# LTEW_WPC_RCVR.net
KiCad netlist of a schematic drawn in Altium Designer
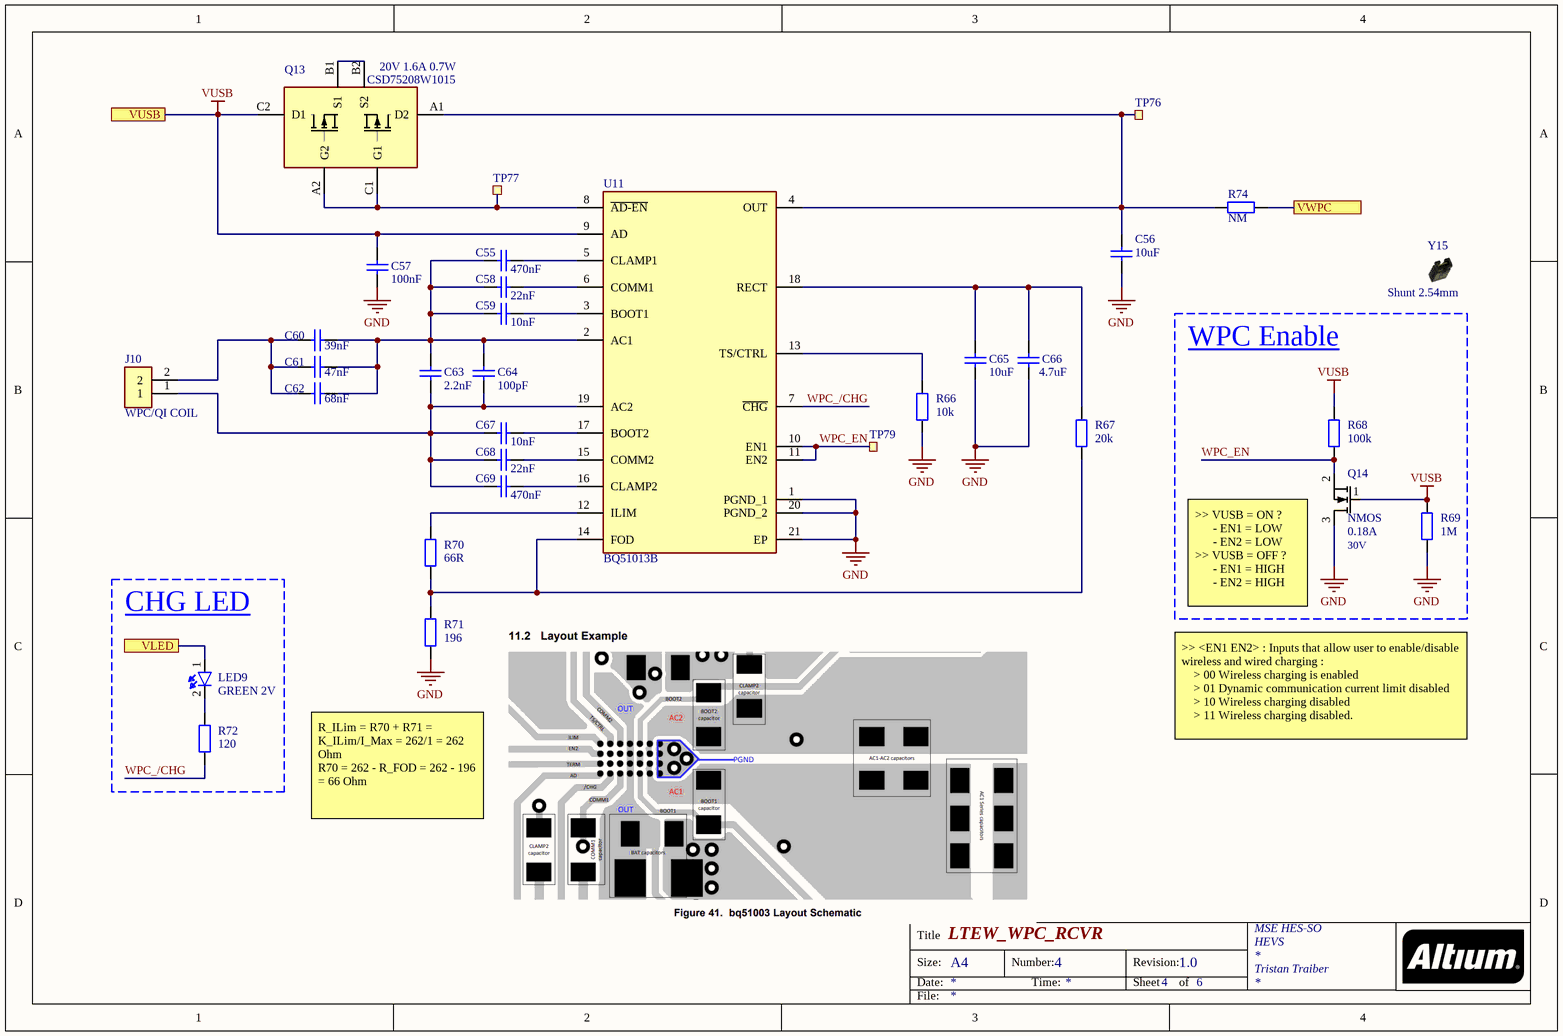
[diagram p0: LTEW_WPC_RCVR.SchDoc]

(export (version "E")
  (design (tool "Eeschema 10.0.6"))
  (components
    (comp (ref "C55")
      (value "470nF")
      (footprint "C0603")
      (description "0.47 µF ±10% 25V Ceramic Capacitor X7R 0603 (1608 Metric)")
      (fields (field (name "MANUFACTURER_PART_NUMBER") "GRM188R71E474KA12D"))
      (libsource (lib "LTEWlib") (part "C_470n"))
    )
    (comp (ref "C56")
      (value "10uF")
      (footprint "C0603")
      (description "10 µF ±10% 25V Ceramic Capacitor X5R 0805 (2012 Metric)")
      (fields (field (name "MANUFACTURER_PART_NUMBER") "GRM188R61E106KA73J"))
      (libsource (lib "LTEWlib") (part "C_10u"))
    )
    (comp (ref "C57")
      (value "100nF")
      (footprint "C0603")
      (description "0.1 µF ±10% 25V Condensateurs céramique X7R 0603 (1608 métrique)")
      (fields (field (name "MANUFACTURER_PART_NUMBER") "CL10B104KA8NNNC"))
      (libsource (lib "LTEWlib") (part "C_100n"))
    )
    (comp (ref "C58")
      (value "22nF")
      (footprint "C0603")
      (description "0.022 µF ±10% 25V Ceramic Capacitor X7R 0603 (1608 Metric)")
      (fields (field (name "MANUFACTURER_PART_NUMBER") "C0603C223K3RAC7867"))
      (libsource (lib "LTEWlib") (part "C_22n"))
    )
    (comp (ref "C59")
      (value "10nF")
      (footprint "C0603")
      (description "10000 pF ±5% 25V Condensateurs céramique C0G, NP0 0603 (1608 métrique)")
      (fields (field (name "MANUFACTURER_PART_NUMBER") "C1608C0G1E103J080AA"))
      (libsource (lib "LTEWlib") (part "C_10n"))
    )
    (comp (ref "C60")
      (value "39nF")
      (footprint "C0603")
      (description "0.039 µF ±10% 50V Ceramic Capacitor X7R 0603 (1608 Metric)")
      (fields (field (name "MANUFACTURER_PART_NUMBER") "0603B393K500CT"))
      (libsource (lib "LTEWlib") (part "C_39n"))
    )
    (comp (ref "C61")
      (value "47nF")
      (footprint "C0603")
      (description "0.047 µF ±10% 25V Ceramic Capacitor X7R 0603 (1608 Metric)")
      (fields (field (name "MANUFACTURER_PART_NUMBER") "06033C473KAT2A"))
      (libsource (lib "LTEWlib") (part "C_47n"))
    )
    (comp (ref "C62")
      (value "68nF")
      (footprint "C0603")
      (description "0.068 µF ±10% 25V Ceramic Capacitor X7R 0603 (1608 Metric)")
      (fields (field (name "MANUFACTURER_PART_NUMBER") "0603B683K250CT"))
      (libsource (lib "LTEWlib") (part "C_68n"))
    )
    (comp (ref "C63")
      (value "2.2nF")
      (footprint "C0603")
      (description "2200 pF ±5% 25V Ceramic Capacitor X7R 0603 (1608 Metric)")
      (fields (field (name "MANUFACTURER_PART_NUMBER") "06033C222JAT2A"))
      (libsource (lib "LTEWlib") (part "C_2.2n"))
    )
    (comp (ref "C64")
      (value "100pF")
      (footprint "C0603")
      (description "100 pF ±5% 25V Ceramic Capacitor C0G, NP0 0603 (1608 Metric)")
      (fields (field (name "MANUFACTURER_PART_NUMBER") "06033A101JAT2A"))
      (libsource (lib "LTEWlib") (part "C_100p"))
    )
    (comp (ref "C65")
      (value "10uF")
      (footprint "C0603")
      (description "10 µF ±10% 25V Ceramic Capacitor X5R 0805 (2012 Metric)")
      (fields (field (name "MANUFACTURER_PART_NUMBER") "GRM188R61E106KA73J"))
      (libsource (lib "LTEWlib") (part "C_10u"))
    )
    (comp (ref "C66")
      (value "4.7uF")
      (footprint "C0603")
      (description "4.7 µF ±10% 25V Condensateurs céramique X6S 0603 (1608 métrique)")
      (fields (field (name "MANUFACTURER_PART_NUMBER") "GRM188C81E475KE11D"))
      (libsource (lib "LTEWlib") (part "C_4.7u"))
    )
    (comp (ref "C67")
      (value "10nF")
      (footprint "C0603")
      (description "10000 pF ±5% 25V Condensateurs céramique C0G, NP0 0603 (1608 métrique)")
      (fields (field (name "MANUFACTURER_PART_NUMBER") "C1608C0G1E103J080AA"))
      (libsource (lib "LTEWlib") (part "C_10n"))
    )
    (comp (ref "C68")
      (value "22nF")
      (footprint "C0603")
      (description "0.022 µF ±10% 25V Ceramic Capacitor X7R 0603 (1608 Metric)")
      (fields (field (name "MANUFACTURER_PART_NUMBER") "C0603C223K3RAC7867"))
      (libsource (lib "LTEWlib") (part "C_22n"))
    )
    (comp (ref "C69")
      (value "470nF")
      (footprint "C0603")
      (description "0.47 µF ±10% 25V Ceramic Capacitor X7R 0603 (1608 Metric)")
      (fields (field (name "MANUFACTURER_PART_NUMBER") "GRM188R71E474KA12D"))
      (libsource (lib "LTEWlib") (part "C_470n"))
    )
    (comp (ref "J10")
      (value "WPC/QI COIL")
      (footprint "LTEWlib:23839422")
      (description "2 Position Wire to Board Terminal Block Horizontal with Board 0.138\" (3.50mm) Surface Mount")
      (fields (field (name "MANUFACTURER_PART_NUMBER") "2383942-2"))
      (libsource (lib "LTEWlib") (part "CONN_WPC_IND"))
    )
    (comp (ref "LED9")
      (value "GREEN 2V")
      (footprint "LTEWlib:LEDC1608X80N")
      (description "Green 570nm LED Indication - Discrete 2V 0603 (1608 Metric)")
      (fields (field (name "MANUFACTURER_PART_NUMBER") "150060VS75000"))
      (libsource (lib "LTEWlib") (part "LED_G"))
    )
    (comp (ref "Q13")
      (value "20V 1.6A 0.7W")
      (footprint "LTEWlib:BGA6C50P2X3_95X145X62")
      (description "Mosfet Array 2 P-Channel (Dual) Common Source 20V 1.6A 750mW Surface Mount 6-DSBGA (1x1.5)")
      (fields (field (name "MANUFACTURER_PART_NUMBER") "CSD75208W1015"))
      (libsource (lib "LTEWlib") (part "MOS_2PCH"))
    )
    (comp (ref "Q14")
      (value "NMOS")
      (footprint "LTEWlib:SOT65P210X110-3N")
      (description "N-Channel 30 V 180mA (Ta) 260mW (Ta), 1.1W (Tc) Surface Mount SOT-323")
      (fields
        (field (name "MANUFACTURER_PART_NUMBER") "NX3020NAKW")
        (field (name "VALUE2") "0.18A")
        (field (name "ALTIUM_VALUE") "30V")
      )
      (libsource (lib "LTEWlib") (part "MOS-N"))
    )
    (comp (ref "R66")
      (value "10k")
      (footprint "RES0603")
      (description "10 kOhms ±1% 0.1W, 1/10W Chip Resistor 0603 (1608 Metric) Moisture Resistant Thick Film")
      (fields (field (name "MANUFACTURER_PART_NUMBER") "RC0805FR-0710KL"))
      (libsource (lib "LTEWlib") (part "R_10k"))
    )
    (comp (ref "R67")
      (value "20k")
      (footprint "RES0603")
      (description "20 kOhms ±1% 0.1W, 1/10W Chip Resistor 0603 (1608 Metric) Moisture Resistant Thick Film")
      (fields (field (name "MANUFACTURER_PART_NUMBER") "RC0805FR-0710KL"))
      (libsource (lib "LTEWlib") (part "R_20k"))
    )
    (comp (ref "R68")
      (value "100k")
      (footprint "RES0603")
      (description "RES SMD 100K OHM 1% 1/8W 0603")
      (fields (field (name "MANUFACTURER_PART_NUMBER") "RC0805FR-07100KL"))
      (libsource (lib "LTEWlib") (part "R_100k"))
    )
    (comp (ref "R69")
      (value "1M")
      (footprint "RES0603")
      (description "1 MOhms ±1% 0.1W, 1/10W Chip Resistor 0603 (1608 Metric) Automotive AEC-Q200 Thick Film")
      (fields (field (name "MANUFACTURER_PART_NUMBER") "ERJ-3EKF1004V"))
      (libsource (lib "LTEWlib") (part "R_1M"))
    )
    (comp (ref "R70")
      (value "66R")
      (footprint "RES0603")
      (description "66.5 Ohms ±1% 0.1W, 1/10W Chip Resistor 0603 (1608 Metric) Moisture Resistant Thick Film")
      (fields (field (name "MANUFACTURER_PART_NUMBER") "RC0603FR-0766R5L"))
      (libsource (lib "LTEWlib") (part "R_66"))
    )
    (comp (ref "R71")
      (value "196")
      (footprint "RES0603")
      (description "196 Ohms ±1% 0.1W, 1/10W Chip Resistor 0603 (1608 Metric) Moisture Resistant Thick Film")
      (fields (field (name "MANUFACTURER_PART_NUMBER") "RC0603FR-07196RL"))
      (libsource (lib "LTEWlib") (part "R_196"))
    )
    (comp (ref "R72")
      (value "120")
      (footprint "RES0603")
      (description "1 MOhms ±1% 0.1W, 1/10W Chip Resistor 0603 (1608 Metric) Automotive AEC-Q200 Thick Film")
      (fields (field (name "MANUFACTURER_PART_NUMBER") "CRGCQ0603F120R"))
      (libsource (lib "LTEWlib") (part "R_120"))
    )
    (comp (ref "R74")
      (value "NM")
      (footprint "RES0603")
      (description "8.66 MOhms ±1% 0,1W, 1/10W Pavé résistif 0603 (1608 métrique) AutomobileAEC-Q200 Couche épaisse")
      (fields (field (name "MANUFACTURER_PART_NUMBER") "CRCW06038M66FKEA"))
      (libsource (lib "LTEWlib") (part "R_8.66M"))
    )
    (comp (ref "TP76")
      (value "Ø1.0mm,SMD")
      (footprint "TP_SMD_Ø0.8mm")
      (description "0.8 mm circular SMD testpad")
      (fields
        (field (name "PART NUMBER") "TP_SMD_Ø1.0MM")
        (field (name "MANUFACTURER") "Nordic Semiconductor")
      )
      (libsource (lib "LTEWlib") (part "TP_SMD"))
    )
    (comp (ref "TP77")
      (value "Ø1.0mm,SMD")
      (footprint "TP_SMD_Ø0.8mm")
      (description "0.8 mm circular SMD testpad")
      (fields
        (field (name "PART NUMBER") "TP_SMD_Ø1.0MM")
        (field (name "MANUFACTURER") "Nordic Semiconductor")
      )
      (libsource (lib "") (part "TP_SMD_1"))
    )
    (comp (ref "TP79")
      (value "Ø1.0mm,SMD")
      (footprint "TP_SMD_Ø0.8mm")
      (description "0.8 mm circular SMD testpad")
      (fields
        (field (name "PART NUMBER") "TP_SMD_Ø1.0MM")
        (field (name "MANUFACTURER") "Nordic Semiconductor")
      )
      (libsource (lib "LTEWlib") (part "TP_SMD"))
    )
    (comp (ref "U11")
      (value "BQ51013B")
      (footprint "LTEWlib:BQ51050BRHLR")
      (description "Wireless Power Receiver PMIC 20-VQFN (3.5x4.5)")
      (fields (field (name "MANUFACTURER_PART_NUMBER") "BQ51013BRHLR"))
      (libsource (lib "LTEWlib") (part "IC_WPC_VQFN"))
    )
    (comp (ref "Y15")
      (value "Shunt 2.54mm")
      (footprint "Shunt_2.54mm_Horizontal")
      (description "Shunt Jumper 2.54mm Black")
      (fields (field (name "MANUFACTURER PART NUMBER") "SPC02SYAN"))
      (libsource (lib "LTEWlib") (part "SHUNT JUMPER 2.54mm BLACK GOLD Horizontal"))
    )
  )
  (nets
    (net (code "1") (name "/VLED") (class "Default")
      (node (ref "LED9") (pin "1") (pinfunction "A_1") (pintype "passive"))
    )
    (net (code "2") (name "/VWPC") (class "Default")
      (node (ref "R74") (pin "1") (pinfunction "1_1") (pintype "passive"))
    )
    (net (code "3") (name "/WPC_EN") (class "Default")
      (node (ref "Q14") (pin "2") (pinfunction "S_2") (pintype "passive"))
      (node (ref "R68") (pin "1") (pinfunction "1_1") (pintype "passive"))
      (node (ref "TP79") (pin "1") (pinfunction "1_1") (pintype "passive"))
      (node (ref "U11") (pin "10") (pinfunction "EN1_10") (pintype "passive"))
      (node (ref "U11") (pin "11") (pinfunction "EN2_11") (pintype "passive"))
    )
    (net (code "4") (name "/WPC_{slash}CHG") (class "Default")
      (node (ref "R72") (pin "1") (pinfunction "1_1") (pintype "passive"))
      (node (ref "U11") (pin "7") (pinfunction "~{CHG}_7") (pintype "passive"))
    )
    (net (code "5") (name "GND") (class "Default")
      (node (ref "C56") (pin "1") (pinfunction "1_1") (pintype "passive"))
      (node (ref "C57") (pin "1") (pinfunction "1_1") (pintype "passive"))
      (node (ref "C65") (pin "1") (pinfunction "1_1") (pintype "passive"))
      (node (ref "C66") (pin "1") (pinfunction "1_1") (pintype "passive"))
      (node (ref "Q14") (pin "3") (pinfunction "D_3") (pintype "passive"))
      (node (ref "R66") (pin "1") (pinfunction "1_1") (pintype "passive"))
      (node (ref "R69") (pin "1") (pinfunction "1_1") (pintype "passive"))
      (node (ref "R71") (pin "1") (pinfunction "1_1") (pintype "passive"))
      (node (ref "U11") (pin "1") (pinfunction "PGND_1_1") (pintype "passive"))
      (node (ref "U11") (pin "20") (pinfunction "PGND_2_20") (pintype "passive"))
      (node (ref "U11") (pin "21") (pinfunction "EP_21") (pintype "passive"))
    )
    (net (code "6") (name "Net-(C60-Pad1)") (class "Default")
      (node (ref "C60") (pin "1") (pinfunction "1_1") (pintype "passive"))
      (node (ref "C61") (pin "1") (pinfunction "1_1") (pintype "passive"))
      (node (ref "C62") (pin "1") (pinfunction "1_1") (pintype "passive"))
      (node (ref "J10") (pin "2") (pinfunction "2_2") (pintype "passive"))
    )
    (net (code "7") (name "Net-(LED9-K)") (class "Default")
      (node (ref "LED9") (pin "2") (pinfunction "K_2") (pintype "passive"))
      (node (ref "R72") (pin "2") (pinfunction "2_2") (pintype "passive"))
    )
    (net (code "8") (name "Net-(Q13-D2)") (class "Default")
      (node (ref "C56") (pin "2") (pinfunction "2_2") (pintype "passive"))
      (node (ref "Q13") (pin "A1") (pinfunction "D2_A1") (pintype "passive"))
      (node (ref "R74") (pin "2") (pinfunction "2_2") (pintype "passive"))
      (node (ref "TP76") (pin "1") (pinfunction "1_1") (pintype "passive"))
      (node (ref "U11") (pin "4") (pinfunction "OUT_4") (pintype "passive"))
    )
    (net (code "9") (name "Net-(Q13-G1)") (class "Default")
      (node (ref "Q13") (pin "A2") (pinfunction "G2_A2") (pintype "passive"))
      (node (ref "Q13") (pin "C1") (pinfunction "G1_C1") (pintype "passive"))
      (node (ref "TP77") (pin "1") (pinfunction "1_1") (pintype "passive"))
      (node (ref "U11") (pin "8") (pinfunction "~{AD-EN}_8") (pintype "passive"))
    )
    (net (code "10") (name "Net-(Q13-S1)") (class "Default")
      (node (ref "Q13") (pin "B1") (pinfunction "S1_B1") (pintype "passive"))
      (node (ref "Q13") (pin "B2") (pinfunction "S2_B2") (pintype "passive"))
    )
    (net (code "11") (name "Net-(U11-AC1)") (class "Default")
      (node (ref "C55") (pin "1") (pinfunction "1_1") (pintype "passive"))
      (node (ref "C58") (pin "1") (pinfunction "1_1") (pintype "passive"))
      (node (ref "C59") (pin "1") (pinfunction "1_1") (pintype "passive"))
      (node (ref "C60") (pin "2") (pinfunction "2_2") (pintype "passive"))
      (node (ref "C61") (pin "2") (pinfunction "2_2") (pintype "passive"))
      (node (ref "C62") (pin "2") (pinfunction "2_2") (pintype "passive"))
      (node (ref "C63") (pin "2") (pinfunction "2_2") (pintype "passive"))
      (node (ref "C64") (pin "2") (pinfunction "2_2") (pintype "passive"))
      (node (ref "U11") (pin "2") (pinfunction "AC1_2") (pintype "passive"))
    )
    (net (code "12") (name "Net-(U11-AC2)") (class "Default")
      (node (ref "C63") (pin "1") (pinfunction "1_1") (pintype "passive"))
      (node (ref "C64") (pin "1") (pinfunction "1_1") (pintype "passive"))
      (node (ref "C67") (pin "1") (pinfunction "1_1") (pintype "passive"))
      (node (ref "C68") (pin "1") (pinfunction "1_1") (pintype "passive"))
      (node (ref "C69") (pin "1") (pinfunction "1_1") (pintype "passive"))
      (node (ref "J10") (pin "1") (pinfunction "1_1") (pintype "passive"))
      (node (ref "U11") (pin "19") (pinfunction "AC2_19") (pintype "passive"))
    )
    (net (code "13") (name "Net-(U11-BOOT1)") (class "Default")
      (node (ref "C59") (pin "2") (pinfunction "2_2") (pintype "passive"))
      (node (ref "U11") (pin "3") (pinfunction "BOOT1_3") (pintype "passive"))
    )
    (net (code "14") (name "Net-(U11-BOOT2)") (class "Default")
      (node (ref "C67") (pin "2") (pinfunction "2_2") (pintype "passive"))
      (node (ref "U11") (pin "17") (pinfunction "BOOT2_17") (pintype "passive"))
    )
    (net (code "15") (name "Net-(U11-CLAMP1)") (class "Default")
      (node (ref "C55") (pin "2") (pinfunction "2_2") (pintype "passive"))
      (node (ref "U11") (pin "5") (pinfunction "CLAMP1_5") (pintype "passive"))
    )
    (net (code "16") (name "Net-(U11-CLAMP2)") (class "Default")
      (node (ref "C69") (pin "2") (pinfunction "2_2") (pintype "passive"))
      (node (ref "U11") (pin "16") (pinfunction "CLAMP2_16") (pintype "passive"))
    )
    (net (code "17") (name "Net-(U11-COMM1)") (class "Default")
      (node (ref "C58") (pin "2") (pinfunction "2_2") (pintype "passive"))
      (node (ref "U11") (pin "6") (pinfunction "COMM1_6") (pintype "passive"))
    )
    (net (code "18") (name "Net-(U11-COMM2)") (class "Default")
      (node (ref "C68") (pin "2") (pinfunction "2_2") (pintype "passive"))
      (node (ref "U11") (pin "15") (pinfunction "COMM2_15") (pintype "passive"))
    )
    (net (code "19") (name "Net-(U11-FOD)") (class "Default")
      (node (ref "R67") (pin "1") (pinfunction "1_1") (pintype "passive"))
      (node (ref "R70") (pin "1") (pinfunction "1_1") (pintype "passive"))
      (node (ref "R71") (pin "2") (pinfunction "2_2") (pintype "passive"))
      (node (ref "U11") (pin "14") (pinfunction "FOD_14") (pintype "passive"))
    )
    (net (code "20") (name "Net-(U11-ILIM)") (class "Default")
      (node (ref "R70") (pin "2") (pinfunction "2_2") (pintype "passive"))
      (node (ref "U11") (pin "12") (pinfunction "ILIM_12") (pintype "passive"))
    )
    (net (code "21") (name "Net-(U11-RECT)") (class "Default")
      (node (ref "C65") (pin "2") (pinfunction "2_2") (pintype "passive"))
      (node (ref "C66") (pin "2") (pinfunction "2_2") (pintype "passive"))
      (node (ref "R67") (pin "2") (pinfunction "2_2") (pintype "passive"))
      (node (ref "U11") (pin "18") (pinfunction "RECT_18") (pintype "passive"))
    )
    (net (code "22") (name "Net-(U11-TS{slash}CTRL)") (class "Default")
      (node (ref "R66") (pin "2") (pinfunction "2_2") (pintype "passive"))
      (node (ref "U11") (pin "13") (pinfunction "TS/CTRL_13") (pintype "passive"))
    )
    (net (code "23") (name "VUSB") (class "Default")
      (node (ref "C57") (pin "2") (pinfunction "2_2") (pintype "passive"))
      (node (ref "Q13") (pin "C2") (pinfunction "D1_C2") (pintype "passive"))
      (node (ref "Q14") (pin "1") (pinfunction "G_1") (pintype "passive"))
      (node (ref "R68") (pin "2") (pinfunction "2_2") (pintype "passive"))
      (node (ref "R69") (pin "2") (pinfunction "2_2") (pintype "passive"))
      (node (ref "U11") (pin "9") (pinfunction "AD_9") (pintype "passive"))
    )
  )
)
